# pwm_2_dc_motor.net
KiCad netlist of a schematic drawn in EAGLE
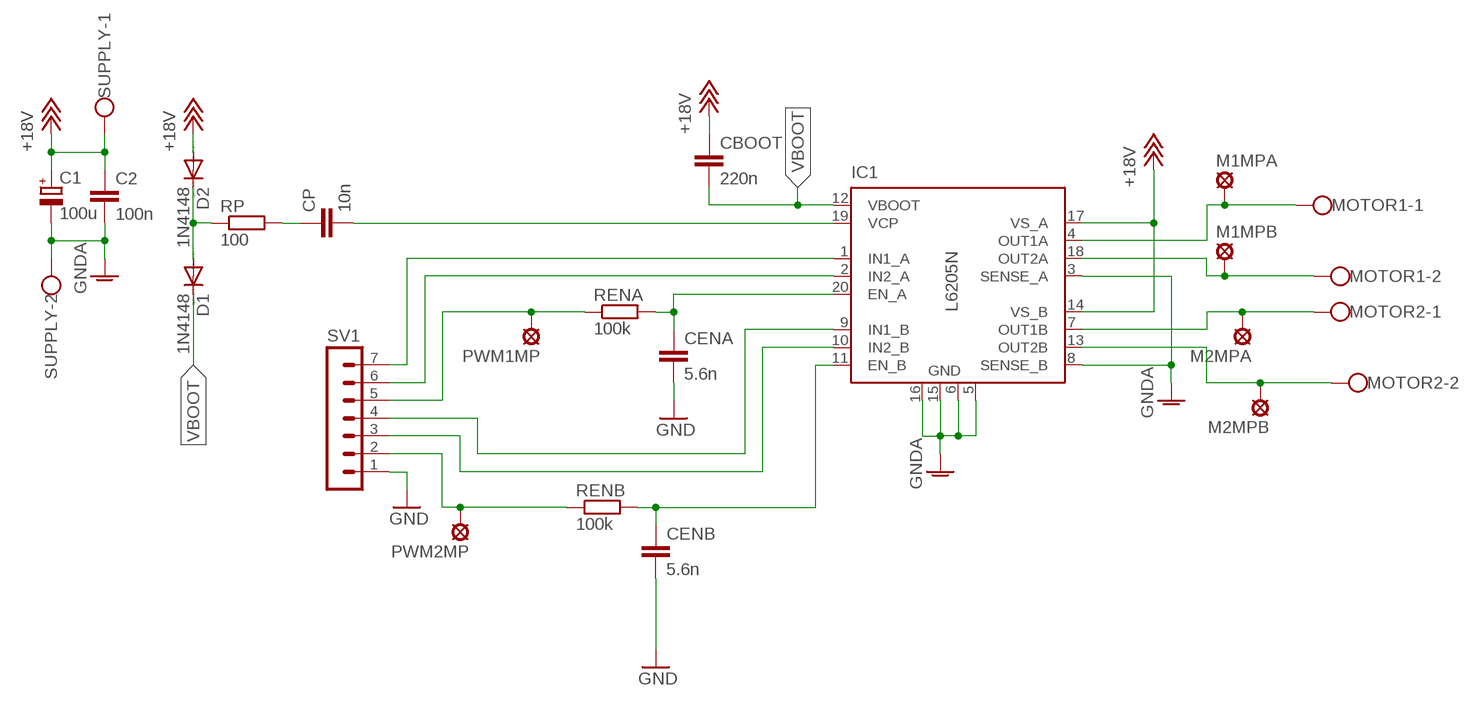
[diagram p0: schematic, sheet 1]

(export (version "E")
  (design (tool "Eeschema 10.0.6"))
  (components
    (comp (ref "C1")
      (value "100u")
      (footprint "eagle-import:E2,5-6E")
      (libsource (lib "eagle-import") (part "CPOL-EUE2,5-6E"))
    )
    (comp (ref "C2")
      (value "100n")
      (footprint "eagle-import:C025-025X050")
      (libsource (lib "eagle-import") (part "C-EU025-025X050"))
    )
    (comp (ref "CBOOT")
      (value "220n")
      (footprint "eagle-import:C025-025X050")
      (libsource (lib "eagle-import") (part "C-EU025-025X050"))
    )
    (comp (ref "CENA")
      (value "5.6n")
      (footprint "eagle-import:C025-025X050")
      (libsource (lib "eagle-import") (part "C-EU025-025X050"))
    )
    (comp (ref "CENB")
      (value "5.6n")
      (footprint "eagle-import:C025-025X050")
      (libsource (lib "eagle-import") (part "C-EU025-025X050"))
    )
    (comp (ref "CP")
      (value "10n")
      (footprint "eagle-import:C025-025X050")
      (libsource (lib "eagle-import") (part "C-EU025-025X050"))
    )
    (comp (ref "D1")
      (value "1N4148")
      (footprint "eagle-import:DO35-10")
      (libsource (lib "eagle-import") (part "1N4148DO35-10"))
    )
    (comp (ref "D2")
      (value "1N4148")
      (footprint "eagle-import:DO35-10")
      (libsource (lib "eagle-import") (part "1N4148DO35-10"))
    )
    (comp (ref "IC1")
      (value "L6205N")
      (footprint "eagle-import:DIL20")
      (fields (field (name "MF") "Arrow Electronics"))
      (libsource (lib "eagle-import") (part "L6205N"))
    )
    (comp (ref "M1MPA")
      (value "LSP10")
      (footprint "eagle-import:LSP10")
      (libsource (lib "eagle-import") (part "LSP10"))
    )
    (comp (ref "M1MPB")
      (value "LSP10")
      (footprint "eagle-import:LSP10")
      (libsource (lib "eagle-import") (part "LSP10"))
    )
    (comp (ref "M2MPA")
      (value "LSP10")
      (footprint "eagle-import:LSP10")
      (libsource (lib "eagle-import") (part "LSP10"))
    )
    (comp (ref "M2MPB")
      (value "LSP10")
      (footprint "eagle-import:LSP10")
      (libsource (lib "eagle-import") (part "LSP10"))
    )
    (comp (ref "MOTOR1")
      (value "W237-102")
      (footprint "eagle-import:W237-102")
      (fields (field (name "MPN") "237-102"))
      (libsource (lib "eagle-import") (part "W237-102"))
    )
    (comp (ref "MOTOR2")
      (value "W237-102")
      (footprint "eagle-import:W237-102")
      (fields (field (name "MPN") "237-102"))
      (libsource (lib "eagle-import") (part "W237-102"))
    )
    (comp (ref "PWM1MP")
      (value "LSP10")
      (footprint "eagle-import:LSP10")
      (libsource (lib "eagle-import") (part "LSP10"))
    )
    (comp (ref "PWM2MP")
      (value "LSP10")
      (footprint "eagle-import:LSP10")
      (libsource (lib "eagle-import") (part "LSP10"))
    )
    (comp (ref "RENA")
      (value "100k")
      (footprint "eagle-import:0207_10")
      (libsource (lib "eagle-import") (part "R-EU_0207/10"))
    )
    (comp (ref "RENB")
      (value "100k")
      (footprint "eagle-import:0207_10")
      (libsource (lib "eagle-import") (part "R-EU_0207/10"))
    )
    (comp (ref "RP")
      (value "100")
      (footprint "eagle-import:0207_12")
      (libsource (lib "eagle-import") (part "resistor_R-EU_0207/12"))
    )
    (comp (ref "SUPPLY")
      (value "W237-102")
      (footprint "eagle-import:W237-102")
      (fields (field (name "MPN") "237-102"))
      (libsource (lib "eagle-import") (part "W237-102"))
    )
    (comp (ref "SV1")
      (value "MA07-1")
      (footprint "eagle-import:MA07-1")
      (libsource (lib "eagle-import") (part "MA07-1"))
    )
  )
  (nets
    (net (code "1") (name "+18V") (class "Default")
      (node (ref "C1") (pin "+") (pinfunction "+_+") (pintype "passive"))
      (node (ref "C2") (pin "1") (pinfunction "1_1") (pintype "passive"))
      (node (ref "CBOOT") (pin "1") (pinfunction "1_1") (pintype "passive"))
      (node (ref "D2") (pin "A") (pinfunction "A_A") (pintype "passive"))
      (node (ref "IC1") (pin "14") (pinfunction "VS_B_14") (pintype "power_in"))
      (node (ref "IC1") (pin "17") (pinfunction "VS_A_17") (pintype "power_in"))
      (node (ref "SUPPLY") (pin "1") (pinfunction "KL_1") (pintype "passive"))
    )
    (net (code "2") (name "GND") (class "Default")
      (node (ref "CENA") (pin "2") (pinfunction "2_2") (pintype "passive"))
      (node (ref "CENB") (pin "2") (pinfunction "2_2") (pintype "passive"))
      (node (ref "SV1") (pin "1") (pinfunction "1_1") (pintype "passive"))
    )
    (net (code "3") (name "GNDA") (class "Default")
      (node (ref "C1") (pin "-") (pinfunction "-_-") (pintype "passive"))
      (node (ref "C2") (pin "2") (pinfunction "2_2") (pintype "passive"))
      (node (ref "IC1") (pin "15") (pinfunction "GND_15") (pintype "power_in"))
      (node (ref "IC1") (pin "16") (pinfunction "GND_16") (pintype "power_in"))
      (node (ref "IC1") (pin "3") (pinfunction "SENSE_A_3") (pintype "input"))
      (node (ref "IC1") (pin "5") (pinfunction "GND_5") (pintype "power_in"))
      (node (ref "IC1") (pin "6") (pinfunction "GND_6") (pintype "power_in"))
      (node (ref "IC1") (pin "8") (pinfunction "SENSE_B_8") (pintype "input"))
      (node (ref "SUPPLY") (pin "2") (pinfunction "KL_2") (pintype "passive"))
    )
    (net (code "4") (name "Net-(CP-Pad1)") (class "Default")
      (node (ref "CP") (pin "1") (pinfunction "1_1") (pintype "passive"))
      (node (ref "RP") (pin "2") (pinfunction "2_2") (pintype "passive"))
    )
    (net (code "5") (name "Net-(D1-PadA)") (class "Default")
      (node (ref "D1") (pin "A") (pinfunction "A_A") (pintype "passive"))
      (node (ref "D2") (pin "C") (pinfunction "C_C") (pintype "passive"))
      (node (ref "RP") (pin "1") (pinfunction "1_1") (pintype "passive"))
    )
    (net (code "6") (name "Net-(IC1-EN_A)") (class "Default")
      (node (ref "CENA") (pin "1") (pinfunction "1_1") (pintype "passive"))
      (node (ref "IC1") (pin "20") (pinfunction "EN_A_20") (pintype "input"))
      (node (ref "RENA") (pin "2") (pinfunction "2_2") (pintype "passive"))
    )
    (net (code "7") (name "Net-(IC1-EN_B)") (class "Default")
      (node (ref "CENB") (pin "1") (pinfunction "1_1") (pintype "passive"))
      (node (ref "IC1") (pin "11") (pinfunction "EN_B_11") (pintype "input"))
      (node (ref "RENB") (pin "2") (pinfunction "2_2") (pintype "passive"))
    )
    (net (code "8") (name "Net-(IC1-IN1_A)") (class "Default")
      (node (ref "IC1") (pin "1") (pinfunction "IN1_A_1") (pintype "input"))
      (node (ref "SV1") (pin "7") (pinfunction "7_7") (pintype "passive"))
    )
    (net (code "9") (name "Net-(IC1-IN1_B)") (class "Default")
      (node (ref "IC1") (pin "9") (pinfunction "IN1_B_9") (pintype "input"))
      (node (ref "SV1") (pin "4") (pinfunction "4_4") (pintype "passive"))
    )
    (net (code "10") (name "Net-(IC1-IN2_A)") (class "Default")
      (node (ref "IC1") (pin "2") (pinfunction "IN2_A_2") (pintype "input"))
      (node (ref "SV1") (pin "6") (pinfunction "6_6") (pintype "passive"))
    )
    (net (code "11") (name "Net-(IC1-IN2_B)") (class "Default")
      (node (ref "IC1") (pin "10") (pinfunction "IN2_B_10") (pintype "input"))
      (node (ref "SV1") (pin "3") (pinfunction "3_3") (pintype "passive"))
    )
    (net (code "12") (name "Net-(IC1-OUT1A)") (class "Default")
      (node (ref "IC1") (pin "4") (pinfunction "OUT1A_4") (pintype "output"))
      (node (ref "M1MPA") (pin "MP") (pinfunction "MP_MP") (pintype "passive"))
      (node (ref "MOTOR1") (pin "1") (pinfunction "KL_1") (pintype "passive"))
    )
    (net (code "13") (name "Net-(IC1-OUT1B)") (class "Default")
      (node (ref "IC1") (pin "7") (pinfunction "OUT1B_7") (pintype "output"))
      (node (ref "M2MPA") (pin "MP") (pinfunction "MP_MP") (pintype "passive"))
      (node (ref "MOTOR2") (pin "1") (pinfunction "KL_1") (pintype "passive"))
    )
    (net (code "14") (name "Net-(IC1-OUT2A)") (class "Default")
      (node (ref "IC1") (pin "18") (pinfunction "OUT2A_18") (pintype "output"))
      (node (ref "M1MPB") (pin "MP") (pinfunction "MP_MP") (pintype "passive"))
      (node (ref "MOTOR1") (pin "2") (pinfunction "KL_2") (pintype "passive"))
    )
    (net (code "15") (name "Net-(IC1-OUT2B)") (class "Default")
      (node (ref "IC1") (pin "13") (pinfunction "OUT2B_13") (pintype "output"))
      (node (ref "M2MPB") (pin "MP") (pinfunction "MP_MP") (pintype "passive"))
      (node (ref "MOTOR2") (pin "2") (pinfunction "KL_2") (pintype "passive"))
    )
    (net (code "16") (name "Net-(IC1-VCP)") (class "Default")
      (node (ref "CP") (pin "2") (pinfunction "2_2") (pintype "passive"))
      (node (ref "IC1") (pin "19") (pinfunction "VCP_19") (pintype "power_in"))
    )
    (net (code "17") (name "Net-(PWM1MP-PadMP)") (class "Default")
      (node (ref "PWM1MP") (pin "MP") (pinfunction "MP_MP") (pintype "passive"))
      (node (ref "RENA") (pin "1") (pinfunction "1_1") (pintype "passive"))
      (node (ref "SV1") (pin "5") (pinfunction "5_5") (pintype "passive"))
    )
    (net (code "18") (name "Net-(PWM2MP-PadMP)") (class "Default")
      (node (ref "PWM2MP") (pin "MP") (pinfunction "MP_MP") (pintype "passive"))
      (node (ref "RENB") (pin "1") (pinfunction "1_1") (pintype "passive"))
      (node (ref "SV1") (pin "2") (pinfunction "2_2") (pintype "passive"))
    )
    (net (code "19") (name "VBOOT") (class "Default")
      (node (ref "CBOOT") (pin "2") (pinfunction "2_2") (pintype "passive"))
      (node (ref "D1") (pin "C") (pinfunction "C_C") (pintype "passive"))
      (node (ref "IC1") (pin "12") (pinfunction "VBOOT_12") (pintype "power_in"))
    )
  )
)
